# GBTx_Power.net
KiCad netlist of a schematic drawn in Altium Designer
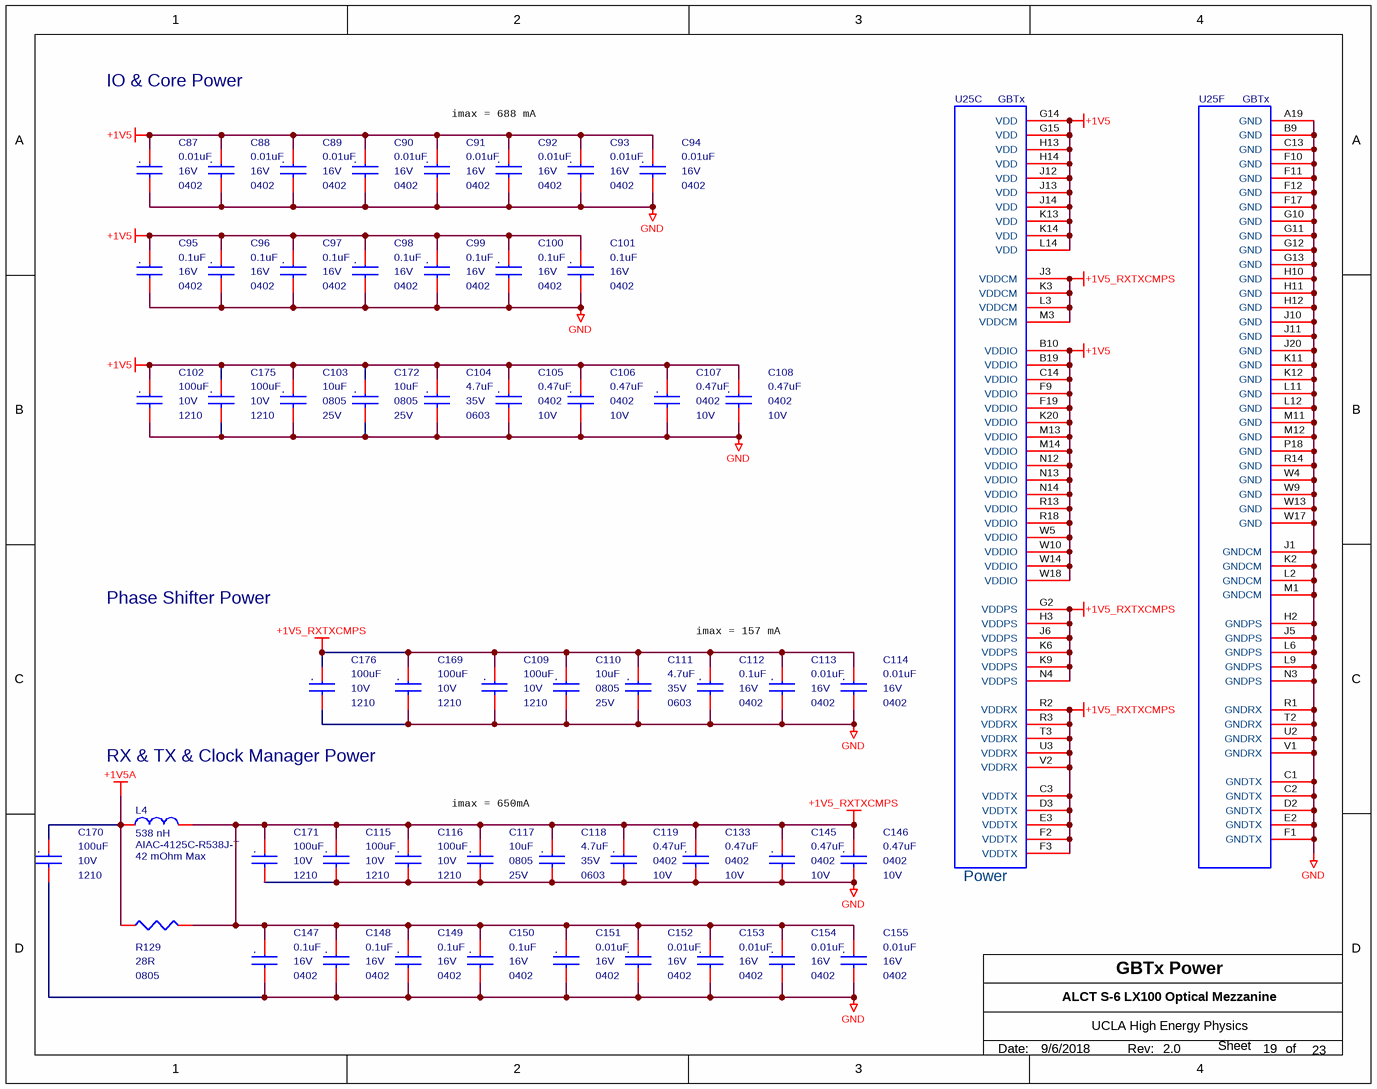
[diagram p0: GBTx_Power.SchDoc]

(export (version "E")
  (design (tool "Eeschema 10.0.6"))
  (components
    (comp (ref "C87")
      (value "0.01uF")
      (footprint "MC_S6/SM/C_0402_IPC")
      (description "CAP CER 10nF 16V X7R 0402")
      (fields
        (field (name "MANUFACTURER") "KEMET")
        (field (name "MANUFACTURER PART NUMBER") "C0402C103K4RACTU")
        (field (name "VOLTAGE - RATED") "16V")
        (field (name "PACKAGE") "0402")
      )
      (libsource (lib "ALCT_MEZ_SPARTAN6_Library") (part "C0402C103K4RACTU"))
    )
    (comp (ref "C88")
      (value "0.01uF")
      (footprint "MC_S6/SM/C_0402_IPC")
      (description "CAP CER 10nF 16V X7R 0402")
      (fields
        (field (name "MANUFACTURER") "KEMET")
        (field (name "MANUFACTURER PART NUMBER") "C0402C103K4RACTU")
        (field (name "VOLTAGE - RATED") "16V")
        (field (name "PACKAGE") "0402")
      )
      (libsource (lib "ALCT_MEZ_SPARTAN6_Library") (part "C0402C103K4RACTU"))
    )
    (comp (ref "C89")
      (value "0.01uF")
      (footprint "MC_S6/SM/C_0402_IPC")
      (description "CAP CER 10nF 16V X7R 0402")
      (fields
        (field (name "MANUFACTURER") "KEMET")
        (field (name "MANUFACTURER PART NUMBER") "C0402C103K4RACTU")
        (field (name "VOLTAGE - RATED") "16V")
        (field (name "PACKAGE") "0402")
      )
      (libsource (lib "ALCT_MEZ_SPARTAN6_Library") (part "C0402C103K4RACTU"))
    )
    (comp (ref "C90")
      (value "0.01uF")
      (footprint "MC_S6/SM/C_0402_IPC")
      (description "CAP CER 10nF 16V X7R 0402")
      (fields
        (field (name "MANUFACTURER") "KEMET")
        (field (name "MANUFACTURER PART NUMBER") "C0402C103K4RACTU")
        (field (name "VOLTAGE - RATED") "16V")
        (field (name "PACKAGE") "0402")
      )
      (libsource (lib "ALCT_MEZ_SPARTAN6_Library") (part "C0402C103K4RACTU"))
    )
    (comp (ref "C91")
      (value "0.01uF")
      (footprint "MC_S6/SM/C_0402_IPC")
      (description "CAP CER 10nF 16V X7R 0402")
      (fields
        (field (name "MANUFACTURER") "KEMET")
        (field (name "MANUFACTURER PART NUMBER") "C0402C103K4RACTU")
        (field (name "VOLTAGE - RATED") "16V")
        (field (name "PACKAGE") "0402")
      )
      (libsource (lib "ALCT_MEZ_SPARTAN6_Library") (part "C0402C103K4RACTU"))
    )
    (comp (ref "C92")
      (value "0.01uF")
      (footprint "MC_S6/SM/C_0402_IPC")
      (description "CAP CER 10nF 16V X7R 0402")
      (fields
        (field (name "MANUFACTURER") "KEMET")
        (field (name "MANUFACTURER PART NUMBER") "C0402C103K4RACTU")
        (field (name "VOLTAGE - RATED") "16V")
        (field (name "PACKAGE") "0402")
      )
      (libsource (lib "ALCT_MEZ_SPARTAN6_Library") (part "C0402C103K4RACTU"))
    )
    (comp (ref "C93")
      (value "0.01uF")
      (footprint "MC_S6/SM/C_0402_IPC")
      (description "CAP CER 10nF 16V X7R 0402")
      (fields
        (field (name "MANUFACTURER") "KEMET")
        (field (name "MANUFACTURER PART NUMBER") "C0402C103K4RACTU")
        (field (name "VOLTAGE - RATED") "16V")
        (field (name "PACKAGE") "0402")
      )
      (libsource (lib "ALCT_MEZ_SPARTAN6_Library") (part "C0402C103K4RACTU"))
    )
    (comp (ref "C94")
      (value "0.01uF")
      (footprint "MC_S6/SM/C_0402_IPC")
      (description "CAP CER 10nF 16V X7R 0402")
      (fields
        (field (name "MANUFACTURER") "KEMET")
        (field (name "MANUFACTURER PART NUMBER") "C0402C103K4RACTU")
        (field (name "VOLTAGE - RATED") "16V")
        (field (name "PACKAGE") "0402")
      )
      (libsource (lib "ALCT_MEZ_SPARTAN6_Library") (part "C0402C103K4RACTU"))
    )
    (comp (ref "C95")
      (value "0.1uF")
      (footprint "MC_S6/SM/C_0402_IPC")
      (description "CAP CER 0.1UF 16V X7R 0402")
      (fields
        (field (name "MANUFACTURER") "KEMET")
        (field (name "MANUFACTURER PART NUMBER") "C0402C104K4RACTU")
        (field (name "VOLTAGE - RATED") "16V")
        (field (name "PACKAGE") "0402")
      )
      (libsource (lib "ALCT_MEZ_SPARTAN6_Library") (part "C0402C104K4RACTU"))
    )
    (comp (ref "C96")
      (value "0.1uF")
      (footprint "MC_S6/SM/C_0402_IPC")
      (description "CAP CER 0.1UF 16V X7R 0402")
      (fields
        (field (name "MANUFACTURER") "KEMET")
        (field (name "MANUFACTURER PART NUMBER") "C0402C104K4RACTU")
        (field (name "VOLTAGE - RATED") "16V")
        (field (name "PACKAGE") "0402")
      )
      (libsource (lib "ALCT_MEZ_SPARTAN6_Library") (part "C0402C104K4RACTU"))
    )
    (comp (ref "C97")
      (value "0.1uF")
      (footprint "MC_S6/SM/C_0402_IPC")
      (description "CAP CER 0.1UF 16V X7R 0402")
      (fields
        (field (name "MANUFACTURER") "KEMET")
        (field (name "MANUFACTURER PART NUMBER") "C0402C104K4RACTU")
        (field (name "VOLTAGE - RATED") "16V")
        (field (name "PACKAGE") "0402")
      )
      (libsource (lib "ALCT_MEZ_SPARTAN6_Library") (part "C0402C104K4RACTU"))
    )
    (comp (ref "C98")
      (value "0.1uF")
      (footprint "MC_S6/SM/C_0402_IPC")
      (description "CAP CER 0.1UF 16V X7R 0402")
      (fields
        (field (name "MANUFACTURER") "KEMET")
        (field (name "MANUFACTURER PART NUMBER") "C0402C104K4RACTU")
        (field (name "VOLTAGE - RATED") "16V")
        (field (name "PACKAGE") "0402")
      )
      (libsource (lib "ALCT_MEZ_SPARTAN6_Library") (part "C0402C104K4RACTU"))
    )
    (comp (ref "C99")
      (value "0.1uF")
      (footprint "MC_S6/SM/C_0402_IPC")
      (description "CAP CER 0.1UF 16V X7R 0402")
      (fields
        (field (name "MANUFACTURER") "KEMET")
        (field (name "MANUFACTURER PART NUMBER") "C0402C104K4RACTU")
        (field (name "VOLTAGE - RATED") "16V")
        (field (name "PACKAGE") "0402")
      )
      (libsource (lib "ALCT_MEZ_SPARTAN6_Library") (part "C0402C104K4RACTU"))
    )
    (comp (ref "C100")
      (value "0.1uF")
      (footprint "MC_S6/SM/C_0402_IPC")
      (description "CAP CER 0.1UF 16V X7R 0402")
      (fields
        (field (name "MANUFACTURER") "KEMET")
        (field (name "MANUFACTURER PART NUMBER") "C0402C104K4RACTU")
        (field (name "VOLTAGE - RATED") "16V")
        (field (name "PACKAGE") "0402")
      )
      (libsource (lib "ALCT_MEZ_SPARTAN6_Library") (part "C0402C104K4RACTU"))
    )
    (comp (ref "C101")
      (value "0.1uF")
      (footprint "MC_S6/SM/C_0402_IPC")
      (description "CAP CER 0.1UF 16V X7R 0402")
      (fields
        (field (name "MANUFACTURER") "KEMET")
        (field (name "MANUFACTURER PART NUMBER") "C0402C104K4RACTU")
        (field (name "VOLTAGE - RATED") "16V")
        (field (name "PACKAGE") "0402")
      )
      (libsource (lib "ALCT_MEZ_SPARTAN6_Library") (part "C0402C104K4RACTU"))
    )
    (comp (ref "C102")
      (value "100uF")
      (footprint "MC_S6/SM/C_1210_IPC")
      (description "CAP CER 100UF 10V X5R 1210")
      (fields
        (field (name "MANUFACTURER") "Taiyo Yuden")
        (field (name "MANUFACTURER PART NUMBER") "LMK325BJ107MM-T")
        (field (name "VOLTAGE - RATED") "10V")
        (field (name "PACKAGE") "1210")
      )
      (libsource (lib "ALCT_MEZ_SPARTAN6_Library") (part "LMK325BJ107MM-T"))
    )
    (comp (ref "C103")
      (value "10uF")
      (footprint "MC_S6/SM/C_0805_IPC")
      (description "CAP CER 10UF 25V X5R 0805")
      (fields
        (field (name "MANUFACTURER") "Murata Electronics North America")
        (field (name "MANUFACTURER PART NUMBER") "GRM21BR61E106KA73L")
        (field (name "VOLTAGE - RATED") "25V")
        (field (name "PACKAGE") "0805")
      )
      (libsource (lib "ALCT_MEZ_SPARTAN6_Library") (part "GRM21BR61E106KA73L"))
    )
    (comp (ref "C104")
      (value "4.7uF")
      (footprint "MC_S6/SM/C_0603_IPC")
      (description "CAP CER 4.7UF 35V X5R 0603")
      (fields
        (field (name "MANUFACTURER") "Murata")
        (field (name "MANUFACTURER PART NUMBER") "GRM188R6YA475KE15D")
        (field (name "VOLTAGE - RATED") "35V")
        (field (name "PACKAGE") "0603")
      )
      (libsource (lib "ALCT_MEZ_SPARTAN6_Library") (part "GRM188R6YA475KE15D"))
    )
    (comp (ref "C105")
      (value "0.47uF")
      (footprint "MC_S6/SM/C_0402_IPC")
      (description "CAP CER 0.47UF 10V X5R 0402")
      (fields
        (field (name "MANUFACTURER") "Murata Electronics North America")
        (field (name "MANUFACTURER PART NUMBER") "GRM155R61A474KE15D")
        (field (name "VOLTAGE - RATED") "10V")
        (field (name "PACKAGE") "0402")
      )
      (libsource (lib "ALCT_MEZ_SPARTAN6_Library") (part "GRM155R61A474KE15D"))
    )
    (comp (ref "C106")
      (value "0.47uF")
      (footprint "MC_S6/SM/C_0402_IPC")
      (description "CAP CER 0.47UF 10V X5R 0402")
      (fields
        (field (name "MANUFACTURER") "Murata Electronics North America")
        (field (name "MANUFACTURER PART NUMBER") "GRM155R61A474KE15D")
        (field (name "VOLTAGE - RATED") "10V")
        (field (name "PACKAGE") "0402")
      )
      (libsource (lib "ALCT_MEZ_SPARTAN6_Library") (part "GRM155R61A474KE15D"))
    )
    (comp (ref "C107")
      (value "0.47uF")
      (footprint "MC_S6/SM/C_0402_IPC")
      (description "CAP CER 0.47UF 10V X5R 0402")
      (fields
        (field (name "MANUFACTURER") "Murata Electronics North America")
        (field (name "MANUFACTURER PART NUMBER") "GRM155R61A474KE15D")
        (field (name "PACKAGE") "0402")
        (field (name "VOLTAGE - RATED") "10V")
      )
      (libsource (lib "ALCT_MEZ_SPARTAN6_Library") (part "GRM155R61A474KE15D"))
    )
    (comp (ref "C108")
      (value "0.47uF")
      (footprint "MC_S6/SM/C_0402_IPC")
      (description "CAP CER 0.47UF 10V X5R 0402")
      (fields
        (field (name "MANUFACTURER") "Murata Electronics North America")
        (field (name "MANUFACTURER PART NUMBER") "GRM155R61A474KE15D")
        (field (name "PACKAGE") "0402")
        (field (name "VOLTAGE - RATED") "10V")
      )
      (libsource (lib "ALCT_MEZ_SPARTAN6_Library") (part "GRM155R61A474KE15D"))
    )
    (comp (ref "C109")
      (value "100uF")
      (footprint "MC_S6/SM/C_1210_IPC")
      (description "CAP CER 100UF 10V X5R 1210")
      (fields
        (field (name "MANUFACTURER") "Taiyo Yuden")
        (field (name "MANUFACTURER PART NUMBER") "LMK325BJ107MM-T")
        (field (name "VOLTAGE - RATED") "10V")
        (field (name "PACKAGE") "1210")
      )
      (libsource (lib "ALCT_MEZ_SPARTAN6_Library") (part "LMK325BJ107MM-T"))
    )
    (comp (ref "C110")
      (value "10uF")
      (footprint "MC_S6/SM/C_0805_IPC")
      (description "CAP CER 10UF 25V X5R 0805")
      (fields
        (field (name "MANUFACTURER") "Murata Electronics North America")
        (field (name "MANUFACTURER PART NUMBER") "GRM21BR61E106KA73L")
        (field (name "VOLTAGE - RATED") "25V")
        (field (name "PACKAGE") "0805")
      )
      (libsource (lib "ALCT_MEZ_SPARTAN6_Library") (part "GRM21BR61E106KA73L"))
    )
    (comp (ref "C111")
      (value "4.7uF")
      (footprint "MC_S6/SM/C_0603_IPC")
      (description "CAP CER 4.7UF 35V X5R 0603")
      (fields
        (field (name "MANUFACTURER") "Murata")
        (field (name "MANUFACTURER PART NUMBER") "GRM188R6YA475KE15D")
        (field (name "VOLTAGE - RATED") "35V")
        (field (name "PACKAGE") "0603")
      )
      (libsource (lib "ALCT_MEZ_SPARTAN6_Library") (part "GRM188R6YA475KE15D"))
    )
    (comp (ref "C112")
      (value "0.1uF")
      (footprint "MC_S6/SM/C_0402_IPC")
      (description "CAP CER 0.1UF 16V X7R 0402")
      (fields
        (field (name "MANUFACTURER") "KEMET")
        (field (name "MANUFACTURER PART NUMBER") "C0402C104K4RACTU")
        (field (name "PACKAGE") "0402")
        (field (name "VOLTAGE - RATED") "16V")
      )
      (libsource (lib "ALCT_MEZ_SPARTAN6_Library") (part "C0402C104K4RACTU"))
    )
    (comp (ref "C113")
      (value "0.01uF")
      (footprint "MC_S6/SM/C_0402_IPC")
      (description "CAP CER 10nF 16V X7R 0402")
      (fields
        (field (name "MANUFACTURER") "KEMET")
        (field (name "MANUFACTURER PART NUMBER") "C0402C103K4RACTU")
        (field (name "VOLTAGE - RATED") "16V")
        (field (name "PACKAGE") "0402")
      )
      (libsource (lib "ALCT_MEZ_SPARTAN6_Library") (part "C0402C103K4RACTU"))
    )
    (comp (ref "C114")
      (value "0.01uF")
      (footprint "MC_S6/SM/C_0402_IPC")
      (description "CAP CER 10nF 16V X7R 0402")
      (fields
        (field (name "MANUFACTURER") "KEMET")
        (field (name "MANUFACTURER PART NUMBER") "C0402C103K4RACTU")
        (field (name "VOLTAGE - RATED") "16V")
        (field (name "PACKAGE") "0402")
      )
      (libsource (lib "ALCT_MEZ_SPARTAN6_Library") (part "C0402C103K4RACTU"))
    )
    (comp (ref "C115")
      (value "100uF")
      (footprint "MC_S6/SM/C_1210_IPC")
      (description "CAP CER 100UF 10V X5R 1210")
      (fields
        (field (name "MANUFACTURER") "Taiyo Yuden")
        (field (name "MANUFACTURER PART NUMBER") "LMK325BJ107MM-T")
        (field (name "VOLTAGE - RATED") "10V")
        (field (name "PACKAGE") "1210")
      )
      (libsource (lib "ALCT_MEZ_SPARTAN6_Library") (part "LMK325BJ107MM-T"))
    )
    (comp (ref "C116")
      (value "100uF")
      (footprint "MC_S6/SM/C_1210_IPC")
      (description "CAP CER 100UF 10V X5R 1210")
      (fields
        (field (name "MANUFACTURER") "Taiyo Yuden")
        (field (name "MANUFACTURER PART NUMBER") "LMK325BJ107MM-T")
        (field (name "VOLTAGE - RATED") "10V")
        (field (name "PACKAGE") "1210")
      )
      (libsource (lib "ALCT_MEZ_SPARTAN6_Library") (part "LMK325BJ107MM-T"))
    )
    (comp (ref "C117")
      (value "10uF")
      (footprint "MC_S6/SM/C_0805_IPC")
      (description "CAP CER 10UF 25V X5R 0805")
      (fields
        (field (name "MANUFACTURER") "Murata Electronics North America")
        (field (name "MANUFACTURER PART NUMBER") "GRM21BR61E106KA73L")
        (field (name "VOLTAGE - RATED") "25V")
        (field (name "PACKAGE") "0805")
      )
      (libsource (lib "ALCT_MEZ_SPARTAN6_Library") (part "GRM21BR61E106KA73L"))
    )
    (comp (ref "C118")
      (value "4.7uF")
      (footprint "MC_S6/SM/C_0603_IPC")
      (description "CAP CER 4.7UF 35V X5R 0603")
      (fields
        (field (name "MANUFACTURER") "Murata")
        (field (name "MANUFACTURER PART NUMBER") "GRM188R6YA475KE15D")
        (field (name "VOLTAGE - RATED") "35V")
        (field (name "PACKAGE") "0603")
      )
      (libsource (lib "ALCT_MEZ_SPARTAN6_Library") (part "GRM188R6YA475KE15D"))
    )
    (comp (ref "C119")
      (value "0.47uF")
      (footprint "MC_S6/SM/C_0402_IPC")
      (description "CAP CER 0.47UF 10V X5R 0402")
      (fields
        (field (name "MANUFACTURER") "Murata Electronics North America")
        (field (name "MANUFACTURER PART NUMBER") "GRM155R61A474KE15D")
        (field (name "VOLTAGE - RATED") "10V")
        (field (name "PACKAGE") "0402")
      )
      (libsource (lib "ALCT_MEZ_SPARTAN6_Library") (part "GRM155R61A474KE15D"))
    )
    (comp (ref "C133")
      (value "0.47uF")
      (footprint "MC_S6/SM/C_0402_IPC")
      (description "CAP CER 0.47UF 10V X5R 0402")
      (fields
        (field (name "MANUFACTURER") "Murata Electronics North America")
        (field (name "MANUFACTURER PART NUMBER") "GRM155R61A474KE15D")
        (field (name "VOLTAGE - RATED") "10V")
        (field (name "PACKAGE") "0402")
      )
      (libsource (lib "ALCT_MEZ_SPARTAN6_Library") (part "GRM155R61A474KE15D"))
    )
    (comp (ref "C145")
      (value "0.47uF")
      (footprint "MC_S6/SM/C_0402_IPC")
      (description "CAP CER 0.47UF 10V X5R 0402")
      (fields
        (field (name "MANUFACTURER") "Murata Electronics North America")
        (field (name "MANUFACTURER PART NUMBER") "GRM155R61A474KE15D")
        (field (name "PACKAGE") "0402")
        (field (name "VOLTAGE - RATED") "10V")
      )
      (libsource (lib "ALCT_MEZ_SPARTAN6_Library") (part "GRM155R61A474KE15D"))
    )
    (comp (ref "C146")
      (value "0.47uF")
      (footprint "MC_S6/SM/C_0402_IPC")
      (description "CAP CER 0.47UF 10V X5R 0402")
      (fields
        (field (name "MANUFACTURER") "Murata Electronics North America")
        (field (name "MANUFACTURER PART NUMBER") "GRM155R61A474KE15D")
        (field (name "PACKAGE") "0402")
        (field (name "VOLTAGE - RATED") "10V")
      )
      (libsource (lib "ALCT_MEZ_SPARTAN6_Library") (part "GRM155R61A474KE15D"))
    )
    (comp (ref "C147")
      (value "0.1uF")
      (footprint "MC_S6/SM/C_0402_IPC")
      (description "CAP CER 0.1UF 16V X7R 0402")
      (fields
        (field (name "MANUFACTURER") "KEMET")
        (field (name "MANUFACTURER PART NUMBER") "C0402C104K4RACTU")
        (field (name "PACKAGE") "0402")
        (field (name "VOLTAGE - RATED") "16V")
      )
      (libsource (lib "ALCT_MEZ_SPARTAN6_Library") (part "C0402C104K4RACTU"))
    )
    (comp (ref "C148")
      (value "0.1uF")
      (footprint "MC_S6/SM/C_0402_IPC")
      (description "CAP CER 0.1UF 16V X7R 0402")
      (fields
        (field (name "MANUFACTURER") "KEMET")
        (field (name "MANUFACTURER PART NUMBER") "C0402C104K4RACTU")
        (field (name "PACKAGE") "0402")
        (field (name "VOLTAGE - RATED") "16V")
      )
      (libsource (lib "ALCT_MEZ_SPARTAN6_Library") (part "C0402C104K4RACTU"))
    )
    (comp (ref "C149")
      (value "0.1uF")
      (footprint "MC_S6/SM/C_0402_IPC")
      (description "CAP CER 0.1UF 16V X7R 0402")
      (fields
        (field (name "MANUFACTURER") "KEMET")
        (field (name "MANUFACTURER PART NUMBER") "C0402C104K4RACTU")
        (field (name "PACKAGE") "0402")
        (field (name "VOLTAGE - RATED") "16V")
      )
      (libsource (lib "ALCT_MEZ_SPARTAN6_Library") (part "C0402C104K4RACTU"))
    )
    (comp (ref "C150")
      (value "0.1uF")
      (footprint "MC_S6/SM/C_0402_IPC")
      (description "CAP CER 0.1UF 16V X7R 0402")
      (fields
        (field (name "MANUFACTURER") "KEMET")
        (field (name "MANUFACTURER PART NUMBER") "C0402C104K4RACTU")
        (field (name "PACKAGE") "0402")
        (field (name "VOLTAGE - RATED") "16V")
      )
      (libsource (lib "ALCT_MEZ_SPARTAN6_Library") (part "C0402C104K4RACTU"))
    )
    (comp (ref "C151")
      (value "0.01uF")
      (footprint "MC_S6/SM/C_0402_IPC")
      (description "CAP CER 10nF 16V X7R 0402")
      (fields
        (field (name "MANUFACTURER") "KEMET")
        (field (name "MANUFACTURER PART NUMBER") "C0402C103K4RACTU")
        (field (name "PACKAGE") "0402")
        (field (name "VOLTAGE - RATED") "16V")
      )
      (libsource (lib "ALCT_MEZ_SPARTAN6_Library") (part "C0402C103K4RACTU"))
    )
    (comp (ref "C152")
      (value "0.01uF")
      (footprint "MC_S6/SM/C_0402_IPC")
      (description "CAP CER 10nF 16V X7R 0402")
      (fields
        (field (name "MANUFACTURER") "KEMET")
        (field (name "MANUFACTURER PART NUMBER") "C0402C103K4RACTU")
        (field (name "PACKAGE") "0402")
        (field (name "VOLTAGE - RATED") "16V")
      )
      (libsource (lib "ALCT_MEZ_SPARTAN6_Library") (part "C0402C103K4RACTU"))
    )
    (comp (ref "C153")
      (value "0.01uF")
      (footprint "MC_S6/SM/C_0402_IPC")
      (description "CAP CER 10nF 16V X7R 0402")
      (fields
        (field (name "MANUFACTURER") "KEMET")
        (field (name "MANUFACTURER PART NUMBER") "C0402C103K4RACTU")
        (field (name "PACKAGE") "0402")
        (field (name "VOLTAGE - RATED") "16V")
      )
      (libsource (lib "ALCT_MEZ_SPARTAN6_Library") (part "C0402C103K4RACTU"))
    )
    (comp (ref "C154")
      (value "0.01uF")
      (footprint "MC_S6/SM/C_0402_IPC")
      (description "CAP CER 10nF 16V X7R 0402")
      (fields
        (field (name "MANUFACTURER") "KEMET")
        (field (name "MANUFACTURER PART NUMBER") "C0402C103K4RACTU")
        (field (name "PACKAGE") "0402")
        (field (name "VOLTAGE - RATED") "16V")
      )
      (libsource (lib "ALCT_MEZ_SPARTAN6_Library") (part "C0402C103K4RACTU"))
    )
    (comp (ref "C155")
      (value "0.01uF")
      (footprint "MC_S6/SM/C_0402_IPC")
      (description "CAP CER 10nF 16V X7R 0402")
      (fields
        (field (name "MANUFACTURER") "KEMET")
        (field (name "MANUFACTURER PART NUMBER") "C0402C103K4RACTU")
        (field (name "PACKAGE") "0402")
        (field (name "VOLTAGE - RATED") "16V")
      )
      (libsource (lib "ALCT_MEZ_SPARTAN6_Library") (part "C0402C103K4RACTU"))
    )
    (comp (ref "C169")
      (value "100uF")
      (footprint "MC_S6/SM/C_1210_IPC")
      (description "CAP CER 100UF 10V X5R 1210")
      (fields
        (field (name "MANUFACTURER") "Taiyo Yuden")
        (field (name "MANUFACTURER PART NUMBER") "LMK325BJ107MM-T")
        (field (name "VOLTAGE - RATED") "10V")
        (field (name "PACKAGE") "1210")
      )
      (libsource (lib "ALCT_MEZ_SPARTAN6_Library") (part "LMK325BJ107MM-T"))
    )
    (comp (ref "C170")
      (value "100uF")
      (footprint "MC_S6/SM/C_1210_IPC")
      (description "CAP CER 100UF 10V X5R 1210")
      (fields
        (field (name "MANUFACTURER") "Taiyo Yuden")
        (field (name "MANUFACTURER PART NUMBER") "LMK325BJ107MM-T")
        (field (name "VOLTAGE - RATED") "10V")
        (field (name "PACKAGE") "1210")
      )
      (libsource (lib "ALCT_MEZ_SPARTAN6_Library") (part "LMK325BJ107MM-T"))
    )
    (comp (ref "C171")
      (value "100uF")
      (footprint "MC_S6/SM/C_1210_IPC")
      (description "CAP CER 100UF 10V X5R 1210")
      (fields
        (field (name "MANUFACTURER") "Taiyo Yuden")
        (field (name "MANUFACTURER PART NUMBER") "LMK325BJ107MM-T")
        (field (name "VOLTAGE - RATED") "10V")
        (field (name "PACKAGE") "1210")
      )
      (libsource (lib "ALCT_MEZ_SPARTAN6_Library") (part "LMK325BJ107MM-T"))
    )
    (comp (ref "C172")
      (value "10uF")
      (footprint "MC_S6/SM/C_0805_IPC")
      (description "CAP CER 10UF 25V X5R 0805")
      (fields
        (field (name "MANUFACTURER") "Murata Electronics North America")
        (field (name "MANUFACTURER PART NUMBER") "GRM21BR61E106KA73L")
        (field (name "VOLTAGE - RATED") "25V")
        (field (name "PACKAGE") "0805")
      )
      (libsource (lib "ALCT_MEZ_SPARTAN6_Library") (part "GRM21BR61E106KA73L"))
    )
    (comp (ref "C175")
      (value "100uF")
      (footprint "MC_S6/SM/C_1210_IPC")
      (description "CAP CER 100UF 10V X5R 1210")
      (fields
        (field (name "MANUFACTURER") "Taiyo Yuden")
        (field (name "MANUFACTURER PART NUMBER") "LMK325BJ107MM-T")
        (field (name "VOLTAGE - RATED") "10V")
        (field (name "PACKAGE") "1210")
      )
      (libsource (lib "ALCT_MEZ_SPARTAN6_Library") (part "LMK325BJ107MM-T"))
    )
    (comp (ref "C176")
      (value "100uF")
      (footprint "MC_S6/SM/C_1210_IPC")
      (description "CAP CER 100UF 10V X5R 1210")
      (fields
        (field (name "MANUFACTURER") "Taiyo Yuden")
        (field (name "MANUFACTURER PART NUMBER") "LMK325BJ107MM-T")
        (field (name "VOLTAGE - RATED") "10V")
        (field (name "PACKAGE") "1210")
      )
      (libsource (lib "ALCT_MEZ_SPARTAN6_Library") (part "LMK325BJ107MM-T"))
    )
    (comp (ref "L4")
      (value "538 nH")
      (footprint "AIAC-4125C-R538J")
      (description "IND 538NH 2A 42 MOHM SMD")
      (fields
        (field (name "MANUFACTURER") "Abracon LLC")
        (field (name "TOLERANCE") "±5%")
        (field (name "MANUFACTURER PART NUMBER") "AIAC-4125C-R538J-T")
        (field (name "DC RESISTANCE (DCR)") "42 mOhm Max")
      )
      (libsource (lib "ALCT_MEZ_SPARTAN6_Library") (part "AIAC-4125C-R538J"))
    )
    (comp (ref "R129")
      (value "28R")
      (footprint "MC_S6/SM/R_0805_IPC")
      (description "RES SMD 28 OHM 1% 1/8W 0805")
      (fields
        (field (name "MANUFACTURER") "Vishay Dale")
        (field (name "MANUFACTURER PART NUMBER") "CRCW080528R0FKEA")
        (field (name "SUPPLIER DEVICE PACKAGE") "0805")
      )
      (libsource (lib "ALCT_MEZ_SPARTAN6_Library") (part "CRCW080528R0FKEA"))
    )
    (comp (ref "U25")
      (value "GBTx")
      (footprint "BGA400 GBT")
      (libsource (lib "ALCT_MEZ_SPARTAN6_Library") (part "GBTx"))
    )
  )
  (nets
    (net (code "1") (name "+1V5") (class "Default")
      (node (ref "C100") (pin "1") (pinfunction "1_1") (pintype "passive"))
      (node (ref "C101") (pin "1") (pinfunction "1_1") (pintype "passive"))
      (node (ref "C102") (pin "1") (pinfunction "1_1") (pintype "passive"))
      (node (ref "C103") (pin "1") (pinfunction "1_1") (pintype "passive"))
      (node (ref "C104") (pin "1") (pinfunction "1_1") (pintype "passive"))
      (node (ref "C105") (pin "1") (pinfunction "1_1") (pintype "passive"))
      (node (ref "C106") (pin "1") (pinfunction "1_1") (pintype "passive"))
      (node (ref "C107") (pin "1") (pinfunction "1_1") (pintype "passive"))
      (node (ref "C108") (pin "1") (pinfunction "1_1") (pintype "passive"))
      (node (ref "C172") (pin "1") (pinfunction "1_1") (pintype "passive"))
      (node (ref "C175") (pin "1") (pinfunction "1_1") (pintype "passive"))
      (node (ref "C87") (pin "1") (pinfunction "1_1") (pintype "passive"))
      (node (ref "C88") (pin "1") (pinfunction "1_1") (pintype "passive"))
      (node (ref "C89") (pin "1") (pinfunction "1_1") (pintype "passive"))
      (node (ref "C90") (pin "1") (pinfunction "1_1") (pintype "passive"))
      (node (ref "C91") (pin "1") (pinfunction "1_1") (pintype "passive"))
      (node (ref "C92") (pin "1") (pinfunction "1_1") (pintype "passive"))
      (node (ref "C93") (pin "1") (pinfunction "1_1") (pintype "passive"))
      (node (ref "C94") (pin "1") (pinfunction "1_1") (pintype "passive"))
      (node (ref "C95") (pin "1") (pinfunction "1_1") (pintype "passive"))
      (node (ref "C96") (pin "1") (pinfunction "1_1") (pintype "passive"))
      (node (ref "C97") (pin "1") (pinfunction "1_1") (pintype "passive"))
      (node (ref "C98") (pin "1") (pinfunction "1_1") (pintype "passive"))
      (node (ref "C99") (pin "1") (pinfunction "1_1") (pintype "passive"))
      (node (ref "U25") (pin "B10") (pinfunction "VDDIO_B10") (pintype "power_in"))
      (node (ref "U25") (pin "B19") (pinfunction "VDDIO_B19") (pintype "power_in"))
      (node (ref "U25") (pin "C14") (pinfunction "VDDIO_C14") (pintype "power_in"))
      (node (ref "U25") (pin "F19") (pinfunction "VDDIO_F19") (pintype "power_in"))
      (node (ref "U25") (pin "F9") (pinfunction "VDDIO_F9") (pintype "power_in"))
      (node (ref "U25") (pin "G14") (pinfunction "VDD_G14") (pintype "power_in"))
      (node (ref "U25") (pin "G15") (pinfunction "VDD_G15") (pintype "power_in"))
      (node (ref "U25") (pin "H13") (pinfunction "VDD_H13") (pintype "power_in"))
      (node (ref "U25") (pin "H14") (pinfunction "VDD_H14") (pintype "power_in"))
      (node (ref "U25") (pin "J12") (pinfunction "VDD_J12") (pintype "power_in"))
      (node (ref "U25") (pin "J13") (pinfunction "VDD_J13") (pintype "power_in"))
      (node (ref "U25") (pin "J14") (pinfunction "VDD_J14") (pintype "power_in"))
      (node (ref "U25") (pin "K13") (pinfunction "VDD_K13") (pintype "power_in"))
      (node (ref "U25") (pin "K14") (pinfunction "VDD_K14") (pintype "power_in"))
      (node (ref "U25") (pin "K20") (pinfunction "VDDIO_K20") (pintype "power_in"))
      (node (ref "U25") (pin "L14") (pinfunction "VDD_L14") (pintype "power_in"))
      (node (ref "U25") (pin "M13") (pinfunction "VDDIO_M13") (pintype "power_in"))
      (node (ref "U25") (pin "M14") (pinfunction "VDDIO_M14") (pintype "power_in"))
      (node (ref "U25") (pin "N12") (pinfunction "VDDIO_N12") (pintype "power_in"))
      (node (ref "U25") (pin "N13") (pinfunction "VDDIO_N13") (pintype "power_in"))
      (node (ref "U25") (pin "N14") (pinfunction "VDDIO_N14") (pintype "power_in"))
      (node (ref "U25") (pin "R13") (pinfunction "VDDIO_R13") (pintype "power_in"))
      (node (ref "U25") (pin "R18") (pinfunction "VDDIO_R18") (pintype "power_in"))
      (node (ref "U25") (pin "W10") (pinfunction "VDDIO_W10") (pintype "power_in"))
      (node (ref "U25") (pin "W14") (pinfunction "VDDIO_W14") (pintype "power_in"))
      (node (ref "U25") (pin "W18") (pinfunction "VDDIO_W18") (pintype "power_in"))
      (node (ref "U25") (pin "W5") (pinfunction "VDDIO_W5") (pintype "power_in"))
    )
    (net (code "2") (name "+1V5A") (class "Default")
      (node (ref "C170") (pin "1") (pinfunction "1_1") (pintype "passive"))
      (node (ref "L4") (pin "2") (pinfunction "2_2") (pintype "passive"))
      (node (ref "R129") (pin "1") (pinfunction "1_1") (pintype "passive"))
    )
    (net (code "3") (name "+1V5_RXTXCMPS") (class "Default")
      (node (ref "C109") (pin "1") (pinfunction "1_1") (pintype "passive"))
      (node (ref "C110") (pin "1") (pinfunction "1_1") (pintype "passive"))
      (node (ref "C111") (pin "1") (pinfunction "1_1") (pintype "passive"))
      (node (ref "C112") (pin "1") (pinfunction "1_1") (pintype "passive"))
      (node (ref "C113") (pin "1") (pinfunction "1_1") (pintype "passive"))
      (node (ref "C114") (pin "1") (pinfunction "1_1") (pintype "passive"))
      (node (ref "C115") (pin "1") (pinfunction "1_1") (pintype "passive"))
      (node (ref "C116") (pin "1") (pinfunction "1_1") (pintype "passive"))
      (node (ref "C117") (pin "1") (pinfunction "1_1") (pintype "passive"))
      (node (ref "C118") (pin "1") (pinfunction "1_1") (pintype "passive"))
      (node (ref "C119") (pin "1") (pinfunction "1_1") (pintype "passive"))
      (node (ref "C133") (pin "1") (pinfunction "1_1") (pintype "passive"))
      (node (ref "C145") (pin "1") (pinfunction "1_1") (pintype "passive"))
      (node (ref "C146") (pin "1") (pinfunction "1_1") (pintype "passive"))
      (node (ref "C147") (pin "1") (pinfunction "1_1") (pintype "passive"))
      (node (ref "C148") (pin "1") (pinfunction "1_1") (pintype "passive"))
      (node (ref "C149") (pin "1") (pinfunction "1_1") (pintype "passive"))
      (node (ref "C150") (pin "1") (pinfunction "1_1") (pintype "passive"))
      (node (ref "C151") (pin "1") (pinfunction "1_1") (pintype "passive"))
      (node (ref "C152") (pin "1") (pinfunction "1_1") (pintype "passive"))
      (node (ref "C153") (pin "1") (pinfunction "1_1") (pintype "passive"))
      (node (ref "C154") (pin "1") (pinfunction "1_1") (pintype "passive"))
      (node (ref "C155") (pin "1") (pinfunction "1_1") (pintype "passive"))
      (node (ref "C169") (pin "1") (pinfunction "1_1") (pintype "passive"))
      (node (ref "C171") (pin "1") (pinfunction "1_1") (pintype "passive"))
      (node (ref "C176") (pin "1") (pinfunction "1_1") (pintype "passive"))
      (node (ref "L4") (pin "1") (pinfunction "1_1") (pintype "passive"))
      (node (ref "R129") (pin "2") (pinfunction "2_2") (pintype "passive"))
      (node (ref "U25") (pin "C3") (pinfunction "VDDTX_C3") (pintype "power_in"))
      (node (ref "U25") (pin "D3") (pinfunction "VDDTX_D3") (pintype "power_in"))
      (node (ref "U25") (pin "E3") (pinfunction "VDDTX_E3") (pintype "power_in"))
      (node (ref "U25") (pin "F2") (pinfunction "VDDTX_F2") (pintype "power_in"))
      (node (ref "U25") (pin "F3") (pinfunction "VDDTX_F3") (pintype "power_in"))
      (node (ref "U25") (pin "G2") (pinfunction "VDDPS_G2") (pintype "power_in"))
      (node (ref "U25") (pin "H3") (pinfunction "VDDPS_H3") (pintype "power_in"))
      (node (ref "U25") (pin "J3") (pinfunction "VDDCM_J3") (pintype "power_in"))
      (node (ref "U25") (pin "J6") (pinfunction "VDDPS_J6") (pintype "power_in"))
      (node (ref "U25") (pin "K3") (pinfunction "VDDCM_K3") (pintype "power_in"))
      (node (ref "U25") (pin "K6") (pinfunction "VDDPS_K6") (pintype "power_in"))
      (node (ref "U25") (pin "K9") (pinfunction "VDDPS_K9") (pintype "power_in"))
      (node (ref "U25") (pin "L3") (pinfunction "VDDCM_L3") (pintype "power_in"))
      (node (ref "U25") (pin "M3") (pinfunction "VDDCM_M3") (pintype "power_in"))
      (node (ref "U25") (pin "N4") (pinfunction "VDDPS_N4") (pintype "power_in"))
      (node (ref "U25") (pin "R2") (pinfunction "VDDRX_R2") (pintype "power_in"))
      (node (ref "U25") (pin "R3") (pinfunction "VDDRX_R3") (pintype "power_in"))
      (node (ref "U25") (pin "T3") (pinfunction "VDDRX_T3") (pintype "power_in"))
      (node (ref "U25") (pin "U3") (pinfunction "VDDRX_U3") (pintype "power_in"))
      (node (ref "U25") (pin "V2") (pinfunction "VDDRX_V2") (pintype "power_in"))
    )
    (net (code "4") (name "GND") (class "Default")
      (node (ref "C100") (pin "2") (pinfunction "2_2") (pintype "passive"))
      (node (ref "C101") (pin "2") (pinfunction "2_2") (pintype "passive"))
      (node (ref "C102") (pin "2") (pinfunction "2_2") (pintype "passive"))
      (node (ref "C103") (pin "2") (pinfunction "2_2") (pintype "passive"))
      (node (ref "C104") (pin "2") (pinfunction "2_2") (pintype "passive"))
      (node (ref "C105") (pin "2") (pinfunction "2_2") (pintype "passive"))
      (node (ref "C106") (pin "2") (pinfunction "2_2") (pintype "passive"))
      (node (ref "C107") (pin "2") (pinfunction "2_2") (pintype "passive"))
      (node (ref "C108") (pin "2") (pinfunction "2_2") (pintype "passive"))
      (node (ref "C109") (pin "2") (pinfunction "2_2") (pintype "passive"))
      (node (ref "C110") (pin "2") (pinfunction "2_2") (pintype "passive"))
      (node (ref "C111") (pin "2") (pinfunction "2_2") (pintype "passive"))
      (node (ref "C112") (pin "2") (pinfunction "2_2") (pintype "passive"))
      (node (ref "C113") (pin "2") (pinfunction "2_2") (pintype "passive"))
      (node (ref "C114") (pin "2") (pinfunction "2_2") (pintype "passive"))
      (node (ref "C115") (pin "2") (pinfunction "2_2") (pintype "passive"))
      (node (ref "C116") (pin "2") (pinfunction "2_2") (pintype "passive"))
      (node (ref "C117") (pin "2") (pinfunction "2_2") (pintype "passive"))
      (node (ref "C118") (pin "2") (pinfunction "2_2") (pintype "passive"))
      (node (ref "C119") (pin "2") (pinfunction "2_2") (pintype "passive"))
      (node (ref "C133") (pin "2") (pinfunction "2_2") (pintype "passive"))
      (node (ref "C145") (pin "2") (pinfunction "2_2") (pintype "passive"))
      (node (ref "C146") (pin "2") (pinfunction "2_2") (pintype "passive"))
      (node (ref "C147") (pin "2") (pinfunction "2_2") (pintype "passive"))
      (node (ref "C148") (pin "2") (pinfunction "2_2") (pintype "passive"))
      (node (ref "C149") (pin "2") (pinfunction "2_2") (pintype "passive"))
      (node (ref "C150") (pin "2") (pinfunction "2_2") (pintype "passive"))
      (node (ref "C151") (pin "2") (pinfunction "2_2") (pintype "passive"))
      (node (ref "C152") (pin "2") (pinfunction "2_2") (pintype "passive"))
      (node (ref "C153") (pin "2") (pinfunction "2_2") (pintype "passive"))
      (node (ref "C154") (pin "2") (pinfunction "2_2") (pintype "passive"))
      (node (ref "C155") (pin "2") (pinfunction "2_2") (pintype "passive"))
      (node (ref "C169") (pin "2") (pinfunction "2_2") (pintype "passive"))
      (node (ref "C170") (pin "2") (pinfunction "2_2") (pintype "passive"))
      (node (ref "C171") (pin "2") (pinfunction "2_2") (pintype "passive"))
      (node (ref "C172") (pin "2") (pinfunction "2_2") (pintype "passive"))
      (node (ref "C175") (pin "2") (pinfunction "2_2") (pintype "passive"))
      (node (ref "C176") (pin "2") (pinfunction "2_2") (pintype "passive"))
      (node (ref "C87") (pin "2") (pinfunction "2_2") (pintype "passive"))
      (node (ref "C88") (pin "2") (pinfunction "2_2") (pintype "passive"))
      (node (ref "C89") (pin "2") (pinfunction "2_2") (pintype "passive"))
      (node (ref "C90") (pin "2") (pinfunction "2_2") (pintype "passive"))
      (node (ref "C91") (pin "2") (pinfunction "2_2") (pintype "passive"))
      (node (ref "C92") (pin "2") (pinfunction "2_2") (pintype "passive"))
      (node (ref "C93") (pin "2") (pinfunction "2_2") (pintype "passive"))
      (node (ref "C94") (pin "2") (pinfunction "2_2") (pintype "passive"))
      (node (ref "C95") (pin "2") (pinfunction "2_2") (pintype "passive"))
      (node (ref "C96") (pin "2") (pinfunction "2_2") (pintype "passive"))
      (node (ref "C97") (pin "2") (pinfunction "2_2") (pintype "passive"))
      (node (ref "C98") (pin "2") (pinfunction "2_2") (pintype "passive"))
      (node (ref "C99") (pin "2") (pinfunction "2_2") (pintype "passive"))
      (node (ref "U25") (pin "A19") (pinfunction "GND_A19") (pintype "power_in"))
      (node (ref "U25") (pin "B9") (pinfunction "GND_B9") (pintype "power_in"))
      (node (ref "U25") (pin "C1") (pinfunction "GNDTX_C1") (pintype "power_in"))
      (node (ref "U25") (pin "C13") (pinfunction "GND_C13") (pintype "power_in"))
      (node (ref "U25") (pin "C2") (pinfunction "GNDTX_C2") (pintype "power_in"))
      (node (ref "U25") (pin "D2") (pinfunction "GNDTX_D2") (pintype "power_in"))
      (node (ref "U25") (pin "E2") (pinfunction "GNDTX_E2") (pintype "power_in"))
      (node (ref "U25") (pin "F1") (pinfunction "GNDTX_F1") (pintype "power_in"))
      (node (ref "U25") (pin "F10") (pinfunction "GND_F10") (pintype "power_in"))
      (node (ref "U25") (pin "F11") (pinfunction "GND_F11") (pintype "power_in"))
      (node (ref "U25") (pin "F12") (pinfunction "GND_F12") (pintype "power_in"))
      (node (ref "U25") (pin "F17") (pinfunction "GND_F17") (pintype "power_in"))
      (node (ref "U25") (pin "G10") (pinfunction "GND_G10") (pintype "power_in"))
      (node (ref "U25") (pin "G11") (pinfunction "GND_G11") (pintype "power_in"))
      (node (ref "U25") (pin "G12") (pinfunction "GND_G12") (pintype "power_in"))
      (node (ref "U25") (pin "G13") (pinfunction "GND_G13") (pintype "power_in"))
      (node (ref "U25") (pin "H10") (pinfunction "GND_H10") (pintype "power_in"))
      (node (ref "U25") (pin "H11") (pinfunction "GND_H11") (pintype "power_in"))
      (node (ref "U25") (pin "H12") (pinfunction "GND_H12") (pintype "power_in"))
      (node (ref "U25") (pin "H2") (pinfunction "GNDPS_H2") (pintype "power_in"))
      (node (ref "U25") (pin "J1") (pinfunction "GNDCM_J1") (pintype "power_in"))
      (node (ref "U25") (pin "J10") (pinfunction "GND_J10") (pintype "power_in"))
      (node (ref "U25") (pin "J11") (pinfunction "GND_J11") (pintype "power_in"))
      (node (ref "U25") (pin "J20") (pinfunction "GND_J20") (pintype "power_in"))
      (node (ref "U25") (pin "J5") (pinfunction "GNDPS_J5") (pintype "power_in"))
      (node (ref "U25") (pin "K11") (pinfunction "GND_K11") (pintype "power_in"))
      (node (ref "U25") (pin "K12") (pinfunction "GND_K12") (pintype "power_in"))
      (node (ref "U25") (pin "K2") (pinfunction "GNDCM_K2") (pintype "power_in"))
      (node (ref "U25") (pin "L11") (pinfunction "GND_L11") (pintype "power_in"))
      (node (ref "U25") (pin "L12") (pinfunction "GND_L12") (pintype "power_in"))
      (node (ref "U25") (pin "L2") (pinfunction "GNDCM_L2") (pintype "power_in"))
      (node (ref "U25") (pin "L6") (pinfunction "GNDPS_L6") (pintype "power_in"))
      (node (ref "U25") (pin "L9") (pinfunction "GNDPS_L9") (pintype "power_in"))
      (node (ref "U25") (pin "M1") (pinfunction "GNDCM_M1") (pintype "power_in"))
      (node (ref "U25") (pin "M11") (pinfunction "GND_M11") (pintype "power_in"))
      (node (ref "U25") (pin "M12") (pinfunction "GND_M12") (pintype "power_in"))
      (node (ref "U25") (pin "N3") (pinfunction "GNDPS_N3") (pintype "power_in"))
      (node (ref "U25") (pin "P18") (pinfunction "GND_P18") (pintype "power_in"))
      (node (ref "U25") (pin "R1") (pinfunction "GNDRX_R1") (pintype "power_in"))
      (node (ref "U25") (pin "R14") (pinfunction "GND_R14") (pintype "power_in"))
      (node (ref "U25") (pin "T2") (pinfunction "GNDRX_T2") (pintype "power_in"))
      (node (ref "U25") (pin "U2") (pinfunction "GNDRX_U2") (pintype "power_in"))
      (node (ref "U25") (pin "V1") (pinfunction "GNDRX_V1") (pintype "power_in"))
      (node (ref "U25") (pin "W13") (pinfunction "GND_W13") (pintype "power_in"))
      (node (ref "U25") (pin "W17") (pinfunction "GND_W17") (pintype "power_in"))
      (node (ref "U25") (pin "W4") (pinfunction "GND_W4") (pintype "power_in"))
      (node (ref "U25") (pin "W9") (pinfunction "GND_W9") (pintype "power_in"))
    )
  )
)
